# Tracksoar_1_3.net
KiCad netlist of a schematic drawn in EAGLE
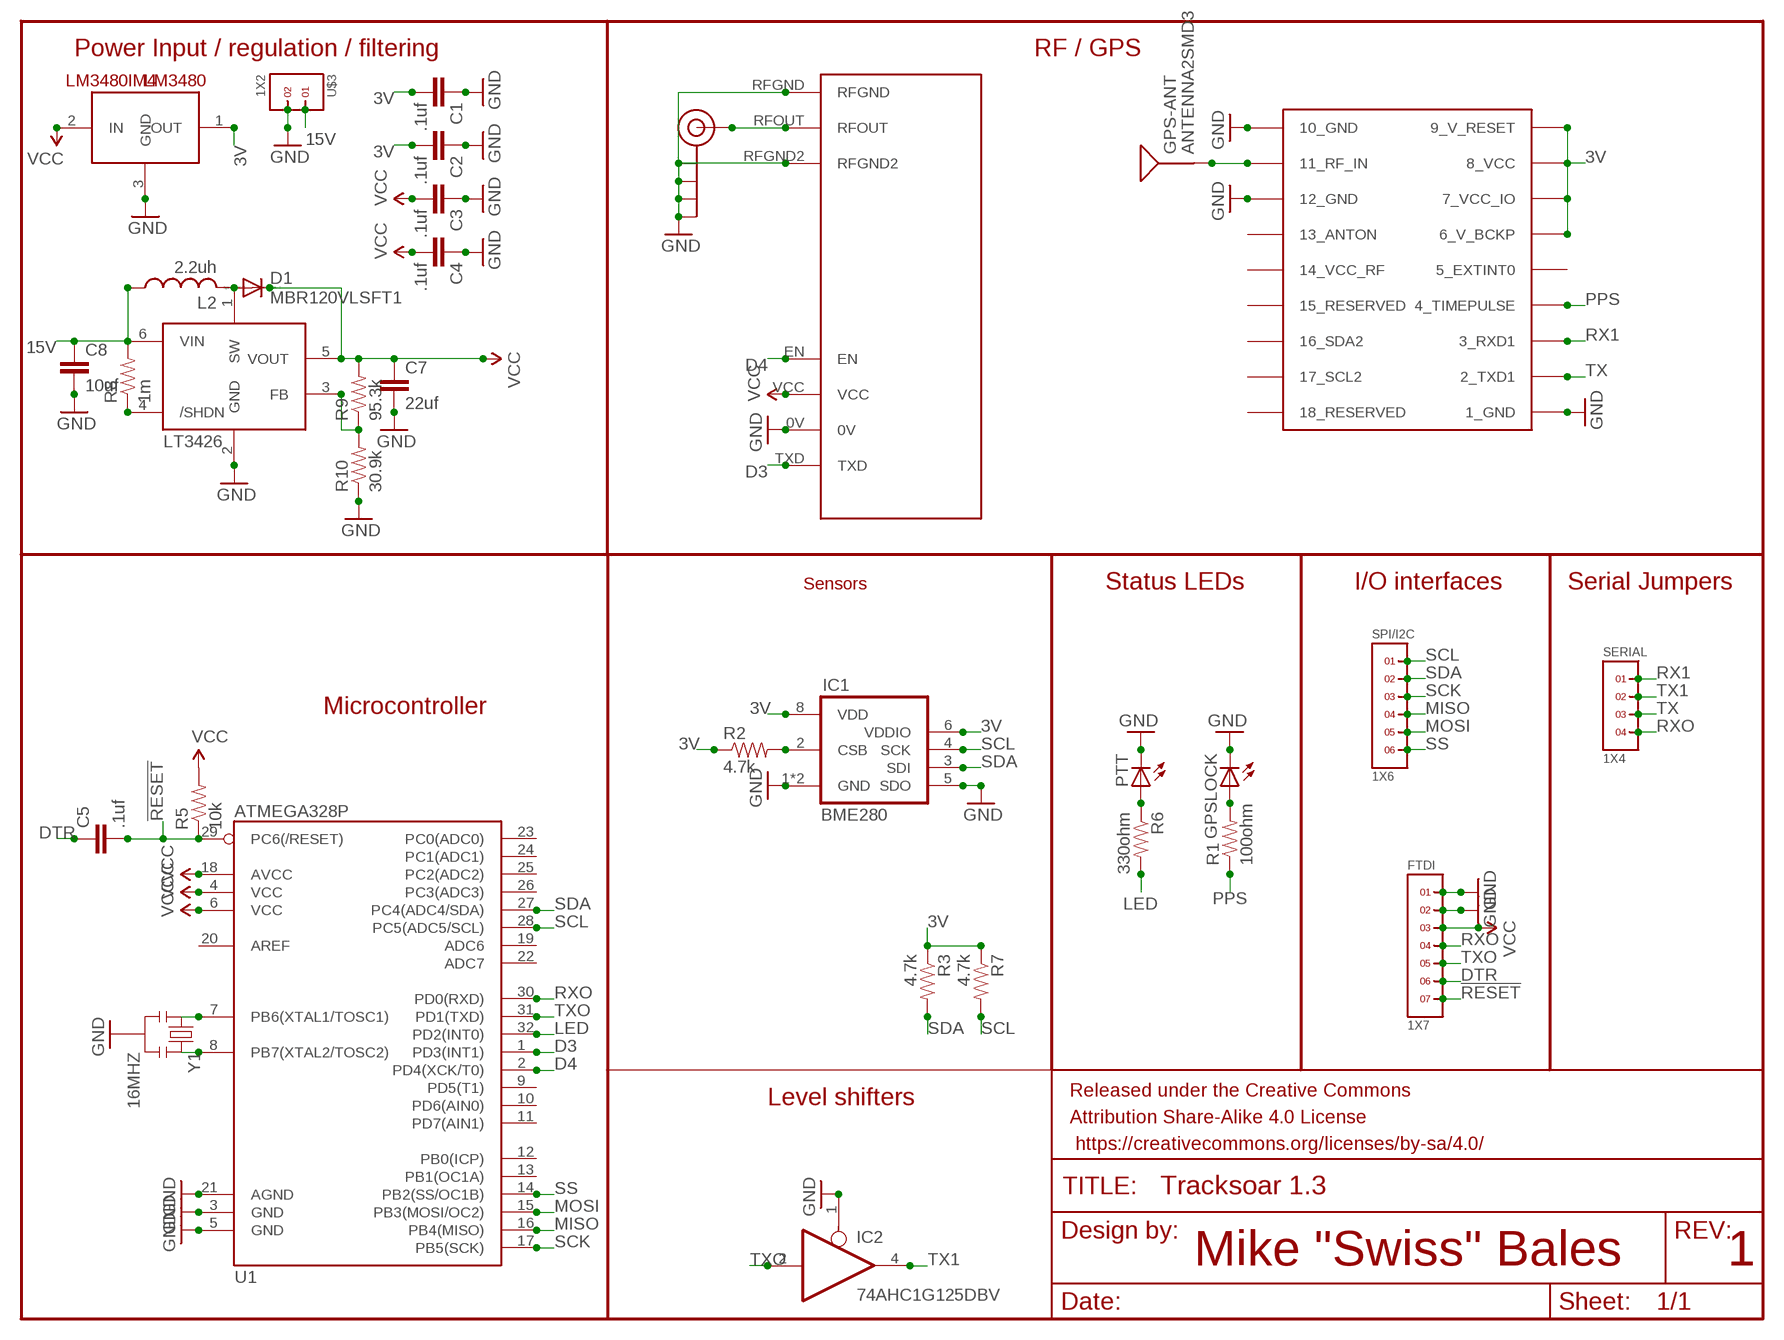
[diagram p0: schematic, sheet 1]

(export (version "E")
  (design (tool "Eeschema 10.0.6"))
  (components
    (comp (ref "C1")
      (value ".1uf")
      (footprint "eagle-import:0805")
      (libsource (lib "eagle-import") (part "CAP0805"))
    )
    (comp (ref "C2")
      (value ".1uf")
      (footprint "eagle-import:0805")
      (libsource (lib "eagle-import") (part "CAP0805"))
    )
    (comp (ref "C3")
      (value ".1uf")
      (footprint "eagle-import:0805")
      (libsource (lib "eagle-import") (part "CAP0805"))
    )
    (comp (ref "C4")
      (value ".1uf")
      (footprint "eagle-import:0805")
      (libsource (lib "eagle-import") (part "CAP0805"))
    )
    (comp (ref "C5")
      (value ".1uf")
      (footprint "eagle-import:0805")
      (libsource (lib "eagle-import") (part "CAP0805"))
    )
    (comp (ref "C7")
      (value "22uf")
      (footprint "eagle-import:0603-CAP")
      (libsource (lib "eagle-import") (part "CAP0603-CAP"))
    )
    (comp (ref "C8")
      (value "10uf")
      (footprint "eagle-import:0805")
      (libsource (lib "eagle-import") (part "CAP0805"))
    )
    (comp (ref "D1")
      (value "MBR120VLSFT1")
      (footprint "eagle-import:SOD123")
      (libsource (lib "eagle-import") (part "DIODE-SOD123"))
    )
    (comp (ref "FRAME1")
      (value "FRAME-LETTER")
      (footprint "eagle-import:CREATIVE_COMMONS")
      (libsource (lib "eagle-import") (part "FRAME-LETTER"))
    )
    (comp (ref "FTDI")
      (value "1X7")
      (footprint "eagle-import:1X7")
      (libsource (lib "eagle-import") (part "1X7"))
    )
    (comp (ref "GPS-ANT")
      (value "ANTENNA2SMD3")
      (footprint "eagle-import:ANTENNA-CHIP4")
      (libsource (lib "eagle-import") (part "ANTENNA2SMD3"))
    )
    (comp (ref "GPSLOCK")
      (value "LEDCHIP-LED0805")
      (footprint "eagle-import:CHIP-LED0805")
      (libsource (lib "eagle-import") (part "LEDCHIP-LED0805"))
    )
    (comp (ref "IC1")
      (value "BME280")
      (footprint "eagle-import:BME280")
      (libsource (lib "eagle-import") (part "BME280"))
    )
    (comp (ref "IC2")
      (value "74AHC1G125DBV")
      (footprint "eagle-import:SOT23-5")
      (libsource (lib "eagle-import") (part "741G125DBVAHC"))
    )
    (comp (ref "J$1")
      (value "SMA_EDGE")
      (footprint "eagle-import:SMA-EDGE")
      (libsource (lib "eagle-import") (part "SMA_EDGE"))
    )
    (comp (ref "L2")
      (value "2.2uh")
      (footprint "eagle-import:L1812")
      (libsource (lib "eagle-import") (part "L-USL1812"))
    )
    (comp (ref "LM3480")
      (value "LM3480IM4")
      (footprint "eagle-import:SOT23-3")
      (libsource (lib "eagle-import") (part "LM3480IM4"))
    )
    (comp (ref "LT3426")
      (value "LT3426")
      (footprint "eagle-import:SOT23-6")
      (libsource (lib "eagle-import") (part "LT3426"))
    )
    (comp (ref "PTT")
      (value "LEDCHIP-LED0805")
      (footprint "eagle-import:CHIP-LED0805")
      (libsource (lib "eagle-import") (part "LEDCHIP-LED0805"))
    )
    (comp (ref "R1")
      (value "100ohm")
      (footprint "eagle-import:0805")
      (libsource (lib "eagle-import") (part "RESISTOR0805-RES"))
    )
    (comp (ref "R2")
      (value "4.7k")
      (footprint "eagle-import:0805")
      (libsource (lib "eagle-import") (part "RESISTOR0805-RES"))
    )
    (comp (ref "R3")
      (value "4.7k")
      (footprint "eagle-import:0805")
      (libsource (lib "eagle-import") (part "RESISTOR0805-RES"))
    )
    (comp (ref "R5")
      (value "10k")
      (footprint "eagle-import:0805")
      (libsource (lib "eagle-import") (part "RESISTOR0805-RES"))
    )
    (comp (ref "R6")
      (value "330ohm")
      (footprint "eagle-import:0805")
      (libsource (lib "eagle-import") (part "RESISTOR0805-RES"))
    )
    (comp (ref "R7")
      (value "4.7k")
      (footprint "eagle-import:0805")
      (libsource (lib "eagle-import") (part "RESISTOR0805-RES"))
    )
    (comp (ref "R8")
      (value "1m")
      (footprint "eagle-import:0805")
      (libsource (lib "eagle-import") (part "RESISTOR0805-RES"))
    )
    (comp (ref "R9")
      (value "95.3k")
      (footprint "eagle-import:0603-RES")
      (libsource (lib "eagle-import") (part "RESISTOR0603"))
    )
    (comp (ref "R10")
      (value "30.9k")
      (footprint "eagle-import:0603-RES")
      (libsource (lib "eagle-import") (part "RESISTOR0603"))
    )
    (comp (ref "SERIAL")
      (value "1X4")
      (footprint "eagle-import:1X4")
      (libsource (lib "eagle-import") (part "1X4"))
    )
    (comp (ref "SPI/I2C")
      (value "1X6")
      (footprint "eagle-import:1X6")
      (libsource (lib "eagle-import") (part "1X6"))
    )
    (comp (ref "U$1")
      (value "UBLOX_MAX")
      (footprint "eagle-import:UBLOX_MAX")
      (libsource (lib "eagle-import") (part "UBLOX_MAX"))
    )
    (comp (ref "U$2")
      (value "RADIOMETRIX-HX1")
      (footprint "eagle-import:RADIOMETRIX-HX1")
      (libsource (lib "eagle-import") (part "RADIOMETRIX-HX1"))
    )
    (comp (ref "U$3")
      (value "1X2")
      (footprint "eagle-import:1X2")
      (libsource (lib "eagle-import") (part "1X2"))
    )
    (comp (ref "U1")
      (value "ATMEGA328P")
      (footprint "eagle-import:MLF32")
      (libsource (lib "eagle-import") (part "ATMEGA168MLF"))
    )
    (comp (ref "Y1")
      (value "16MHZ")
      (footprint "eagle-import:RESONATOR-SMD")
      (libsource (lib "eagle-import") (part "RESONATOR16MHZ"))
    )
  )
  (nets
    (net (code "1") (name "/3V") (class "Default")
      (node (ref "C1") (pin "2") (pinfunction "2_2") (pintype "passive"))
      (node (ref "C2") (pin "2") (pinfunction "2_2") (pintype "passive"))
      (node (ref "IC1") (pin "6") (pinfunction "VDDIO_6") (pintype "power_in"))
      (node (ref "IC1") (pin "8") (pinfunction "VDD_8") (pintype "power_in"))
      (node (ref "LM3480") (pin "1") (pinfunction "OUT_1") (pintype "bidirectional"))
      (node (ref "R2") (pin "1") (pinfunction "1_1") (pintype "passive"))
      (node (ref "R3") (pin "1") (pinfunction "1_1") (pintype "passive"))
      (node (ref "R7") (pin "1") (pinfunction "1_1") (pintype "passive"))
      (node (ref "U$1") (pin "6_V_BCKP") (pinfunction "6_V_BCKP_6_V_BCKP") (pintype "bidirectional"))
      (node (ref "U$1") (pin "7_VCC_IO") (pinfunction "7_VCC_IO_7_VCC_IO") (pintype "power_in"))
      (node (ref "U$1") (pin "8_VCC") (pinfunction "8_VCC_8_VCC") (pintype "power_in"))
      (node (ref "U$1") (pin "9_V_RESET") (pinfunction "9_V_RESET_9_V_RESET") (pintype "power_in"))
    )
    (net (code "2") (name "/15V") (class "Default")
      (node (ref "C8") (pin "1") (pinfunction "1_1") (pintype "passive"))
      (node (ref "L2") (pin "1") (pinfunction "1_1") (pintype "passive"))
      (node (ref "LT3426") (pin "6") (pinfunction "VIN_6") (pintype "input"))
      (node (ref "R8") (pin "2") (pinfunction "2_2") (pintype "passive"))
      (node (ref "U$3") (pin "1") (pinfunction "1_1") (pintype "bidirectional"))
    )
    (net (code "3") (name "/D3") (class "Default")
      (node (ref "U$2") (pin "TXD") (pinfunction "TXD_TXD") (pintype "bidirectional"))
      (node (ref "U1") (pin "1") (pinfunction "PD3(INT1)_1") (pintype "bidirectional"))
    )
    (net (code "4") (name "/D4") (class "Default")
      (node (ref "U$2") (pin "EN") (pinfunction "EN_EN") (pintype "bidirectional"))
      (node (ref "U1") (pin "2") (pinfunction "PD4(XCK/T0)_2") (pintype "bidirectional"))
    )
    (net (code "5") (name "/DTR") (class "Default")
      (node (ref "C5") (pin "1") (pinfunction "1_1") (pintype "passive"))
      (node (ref "FTDI") (pin "6") (pinfunction "6_6") (pintype "bidirectional"))
    )
    (net (code "6") (name "/LED") (class "Default")
      (node (ref "R6") (pin "2") (pinfunction "2_2") (pintype "passive"))
      (node (ref "U1") (pin "32") (pinfunction "PD2(INT0)_32") (pintype "bidirectional"))
    )
    (net (code "7") (name "/MISO") (class "Default")
      (node (ref "SPI/I2C") (pin "4") (pinfunction "4_4") (pintype "bidirectional"))
      (node (ref "U1") (pin "16") (pinfunction "PB4(MISO)_16") (pintype "bidirectional"))
    )
    (net (code "8") (name "/MOSI") (class "Default")
      (node (ref "SPI/I2C") (pin "5") (pinfunction "5_5") (pintype "bidirectional"))
      (node (ref "U1") (pin "15") (pinfunction "PB3(MOSI/OC2)_15") (pintype "bidirectional"))
    )
    (net (code "9") (name "/PPS") (class "Default")
      (node (ref "R1") (pin "1") (pinfunction "1_1") (pintype "passive"))
      (node (ref "U$1") (pin "4_TIMEPULSE") (pinfunction "4_TIMEPULSE_4_TIMEPULSE") (pintype "bidirectional"))
    )
    (net (code "10") (name "/RX1") (class "Default")
      (node (ref "SERIAL") (pin "1") (pinfunction "1_1") (pintype "bidirectional"))
      (node (ref "U$1") (pin "3_RXD1") (pinfunction "3_RXD1_3_RXD1") (pintype "bidirectional"))
    )
    (net (code "11") (name "/RXO") (class "Default")
      (node (ref "FTDI") (pin "4") (pinfunction "4_4") (pintype "bidirectional"))
      (node (ref "SERIAL") (pin "4") (pinfunction "4_4") (pintype "bidirectional"))
      (node (ref "U1") (pin "30") (pinfunction "PD0(RXD)_30") (pintype "bidirectional"))
    )
    (net (code "12") (name "/SCK") (class "Default")
      (node (ref "SPI/I2C") (pin "3") (pinfunction "3_3") (pintype "bidirectional"))
      (node (ref "U1") (pin "17") (pinfunction "PB5(SCK)_17") (pintype "bidirectional"))
    )
    (net (code "13") (name "/SCL") (class "Default")
      (node (ref "IC1") (pin "4") (pinfunction "SCK_4") (pintype "bidirectional"))
      (node (ref "R7") (pin "2") (pinfunction "2_2") (pintype "passive"))
      (node (ref "SPI/I2C") (pin "1") (pinfunction "1_1") (pintype "bidirectional"))
      (node (ref "U1") (pin "28") (pinfunction "PC5(ADC5/SCL)_28") (pintype "bidirectional"))
    )
    (net (code "14") (name "/SDA") (class "Default")
      (node (ref "IC1") (pin "3") (pinfunction "SDI_3") (pintype "bidirectional"))
      (node (ref "R3") (pin "2") (pinfunction "2_2") (pintype "passive"))
      (node (ref "SPI/I2C") (pin "2") (pinfunction "2_2") (pintype "bidirectional"))
      (node (ref "U1") (pin "27") (pinfunction "PC4(ADC4/SDA)_27") (pintype "bidirectional"))
    )
    (net (code "15") (name "/SS") (class "Default")
      (node (ref "SPI/I2C") (pin "6") (pinfunction "6_6") (pintype "bidirectional"))
      (node (ref "U1") (pin "14") (pinfunction "PB2(SS/OC1B)_14") (pintype "bidirectional"))
    )
    (net (code "16") (name "/TX") (class "Default")
      (node (ref "SERIAL") (pin "3") (pinfunction "3_3") (pintype "bidirectional"))
      (node (ref "U$1") (pin "2_TXD1") (pinfunction "2_TXD1_2_TXD1") (pintype "bidirectional"))
    )
    (net (code "17") (name "/TX1") (class "Default")
      (node (ref "IC2") (pin "4") (pinfunction "O_4") (pintype "tri_state"))
      (node (ref "SERIAL") (pin "2") (pinfunction "2_2") (pintype "bidirectional"))
    )
    (net (code "18") (name "/TXO") (class "Default")
      (node (ref "FTDI") (pin "5") (pinfunction "5_5") (pintype "bidirectional"))
      (node (ref "IC2") (pin "2") (pinfunction "I_2") (pintype "input"))
      (node (ref "U1") (pin "31") (pinfunction "PD1(TXD)_31") (pintype "bidirectional"))
    )
    (net (code "19") (name "/~{RESET}") (class "Default")
      (node (ref "C5") (pin "2") (pinfunction "2_2") (pintype "passive"))
      (node (ref "FTDI") (pin "7") (pinfunction "7_7") (pintype "bidirectional"))
      (node (ref "R5") (pin "1") (pinfunction "1_1") (pintype "passive"))
      (node (ref "U1") (pin "29") (pinfunction "PC6(/RESET)_29") (pintype "bidirectional"))
    )
    (net (code "20") (name "GND") (class "Default")
      (node (ref "C1") (pin "1") (pinfunction "1_1") (pintype "passive"))
      (node (ref "C2") (pin "1") (pinfunction "1_1") (pintype "passive"))
      (node (ref "C3") (pin "1") (pinfunction "1_1") (pintype "passive"))
      (node (ref "C4") (pin "1") (pinfunction "1_1") (pintype "passive"))
      (node (ref "C7") (pin "2") (pinfunction "2_2") (pintype "passive"))
      (node (ref "C8") (pin "2") (pinfunction "2_2") (pintype "passive"))
      (node (ref "FTDI") (pin "1") (pinfunction "1_1") (pintype "bidirectional"))
      (node (ref "FTDI") (pin "2") (pinfunction "2_2") (pintype "bidirectional"))
      (node (ref "GPSLOCK") (pin "C") (pinfunction "C_C") (pintype "passive"))
      (node (ref "IC1") (pin "1") (pinfunction "GND_1") (pintype "power_in"))
      (node (ref "IC1") (pin "5") (pinfunction "SDO_5") (pintype "input"))
      (node (ref "IC1") (pin "7") (pinfunction "GND_7") (pintype "power_in"))
      (node (ref "IC2") (pin "1") (pinfunction "OE_1") (pintype "input"))
      (node (ref "J$1") (pin "GND@0") (pinfunction "GND_GND@0") (pintype "bidirectional"))
      (node (ref "J$1") (pin "GND@1") (pinfunction "GND_GND@1") (pintype "bidirectional"))
      (node (ref "J$1") (pin "GND@2") (pinfunction "GND_GND@2") (pintype "bidirectional"))
      (node (ref "J$1") (pin "GND@3") (pinfunction "GND_GND@3") (pintype "bidirectional"))
      (node (ref "LM3480") (pin "3") (pinfunction "GND_3") (pintype "bidirectional"))
      (node (ref "LT3426") (pin "2") (pinfunction "GND_2") (pintype "power_in"))
      (node (ref "PTT") (pin "C") (pinfunction "C_C") (pintype "passive"))
      (node (ref "R10") (pin "1") (pinfunction "1_1") (pintype "passive"))
      (node (ref "U$1") (pin "10_GND") (pinfunction "10_GND_10_GND") (pintype "power_in"))
      (node (ref "U$1") (pin "12_GND") (pinfunction "12_GND_12_GND") (pintype "power_in"))
      (node (ref "U$1") (pin "1_GND") (pinfunction "1_GND_1_GND") (pintype "power_in"))
      (node (ref "U$2") (pin "0V") (pinfunction "0V_0V") (pintype "bidirectional"))
      (node (ref "U$2") (pin "RFGND") (pinfunction "RFGND_RFGND") (pintype "bidirectional"))
      (node (ref "U$2") (pin "RFGND2") (pinfunction "RFGND2_RFGND2") (pintype "bidirectional"))
      (node (ref "U$3") (pin "2") (pinfunction "2_2") (pintype "bidirectional"))
      (node (ref "U1") (pin "21") (pinfunction "AGND_21") (pintype "bidirectional"))
      (node (ref "U1") (pin "3") (pinfunction "GND_3") (pintype "bidirectional"))
      (node (ref "U1") (pin "5") (pinfunction "GND_5") (pintype "bidirectional"))
      (node (ref "Y1") (pin "2") (pinfunction "2_2") (pintype "passive"))
    )
    (net (code "21") (name "Net-(GPS-ANT-SIGNAL)") (class "Default")
      (node (ref "GPS-ANT") (pin "SIG") (pinfunction "SIGNAL_SIG") (pintype "bidirectional"))
      (node (ref "U$1") (pin "11_RF_IN") (pinfunction "11_RF_IN_11_RF_IN") (pintype "bidirectional"))
    )
    (net (code "22") (name "Net-(GPSLOCK-PadA)") (class "Default")
      (node (ref "GPSLOCK") (pin "A") (pinfunction "A_A") (pintype "passive"))
      (node (ref "R1") (pin "2") (pinfunction "2_2") (pintype "passive"))
    )
    (net (code "23") (name "Net-(IC1-CSB)") (class "Default")
      (node (ref "IC1") (pin "2") (pinfunction "CSB_2") (pintype "input"))
      (node (ref "R2") (pin "2") (pinfunction "2_2") (pintype "passive"))
    )
    (net (code "24") (name "Net-(J$1-SIGNAL)") (class "Default")
      (node (ref "J$1") (pin "SIG") (pinfunction "SIGNAL_SIG") (pintype "bidirectional"))
      (node (ref "U$2") (pin "RFOUT") (pinfunction "RFOUT_RFOUT") (pintype "bidirectional"))
    )
    (net (code "25") (name "Net-(LT3426-FB)") (class "Default")
      (node (ref "LT3426") (pin "3") (pinfunction "FB_3") (pintype "input"))
      (node (ref "R10") (pin "2") (pinfunction "2_2") (pintype "passive"))
      (node (ref "R9") (pin "1") (pinfunction "1_1") (pintype "passive"))
    )
    (net (code "26") (name "Net-(LT3426-SW)") (class "Default")
      (node (ref "D1") (pin "A") (pinfunction "A_A") (pintype "passive"))
      (node (ref "L2") (pin "2") (pinfunction "2_2") (pintype "passive"))
      (node (ref "LT3426") (pin "1") (pinfunction "SW_1") (pintype "output"))
    )
    (net (code "27") (name "Net-(LT3426-{slash}SHDN)") (class "Default")
      (node (ref "LT3426") (pin "4") (pinfunction "/SHDN_4") (pintype "input"))
      (node (ref "R8") (pin "1") (pinfunction "1_1") (pintype "passive"))
    )
    (net (code "28") (name "Net-(PTT-PadA)") (class "Default")
      (node (ref "PTT") (pin "A") (pinfunction "A_A") (pintype "passive"))
      (node (ref "R6") (pin "1") (pinfunction "1_1") (pintype "passive"))
    )
    (net (code "29") (name "Net-(U1-PB6(XTAL1{slash}TOSC1))") (class "Default")
      (node (ref "U1") (pin "7") (pinfunction "PB6(XTAL1/TOSC1)_7") (pintype "bidirectional"))
      (node (ref "Y1") (pin "1") (pinfunction "1_1") (pintype "passive"))
    )
    (net (code "30") (name "Net-(U1-PB7(XTAL2{slash}TOSC2))") (class "Default")
      (node (ref "U1") (pin "8") (pinfunction "PB7(XTAL2/TOSC2)_8") (pintype "bidirectional"))
      (node (ref "Y1") (pin "3") (pinfunction "3_3") (pintype "passive"))
    )
    (net (code "31") (name "VCC") (class "Default")
      (node (ref "C3") (pin "2") (pinfunction "2_2") (pintype "passive"))
      (node (ref "C4") (pin "2") (pinfunction "2_2") (pintype "passive"))
      (node (ref "C7") (pin "1") (pinfunction "1_1") (pintype "passive"))
      (node (ref "D1") (pin "C") (pinfunction "C_C") (pintype "passive"))
      (node (ref "FTDI") (pin "3") (pinfunction "3_3") (pintype "bidirectional"))
      (node (ref "LM3480") (pin "2") (pinfunction "IN_2") (pintype "bidirectional"))
      (node (ref "LT3426") (pin "5") (pinfunction "VOUT_5") (pintype "output"))
      (node (ref "R5") (pin "2") (pinfunction "2_2") (pintype "passive"))
      (node (ref "R9") (pin "2") (pinfunction "2_2") (pintype "passive"))
      (node (ref "U$2") (pin "VCC") (pinfunction "VCC_VCC") (pintype "bidirectional"))
      (node (ref "U1") (pin "18") (pinfunction "AVCC_18") (pintype "bidirectional"))
      (node (ref "U1") (pin "4") (pinfunction "VCC_4") (pintype "bidirectional"))
      (node (ref "U1") (pin "6") (pinfunction "VCC_6") (pintype "bidirectional"))
    )
    (net (code "32") (name "unconnected-(U$1-Pad5_EXTINT0)") (class "Default")
      (node (ref "U$1") (pin "5_EXTINT0") (pinfunction "5_EXTINT0_5_EXTINT0") (pintype "bidirectional"))
    )
    (net (code "33") (name "unconnected-(U$1-Pad13_ANTON)") (class "Default")
      (node (ref "U$1") (pin "13_ANTON") (pinfunction "13_ANTON_13_ANTON") (pintype "bidirectional"))
    )
    (net (code "34") (name "unconnected-(U$1-Pad14_VCC_RF)") (class "Default")
      (node (ref "U$1") (pin "14_VCC_RF") (pinfunction "14_VCC_RF_14_VCC_RF") (pintype "bidirectional"))
    )
    (net (code "35") (name "unconnected-(U$1-Pad15_RESERVED)") (class "Default")
      (node (ref "U$1") (pin "15_RESERVED") (pinfunction "15_RESERVED_15_RESERVED") (pintype "bidirectional"))
    )
    (net (code "36") (name "unconnected-(U$1-Pad16_SDA2)") (class "Default")
      (node (ref "U$1") (pin "16_SDA2") (pinfunction "16_SDA2_16_SDA2") (pintype "bidirectional"))
    )
    (net (code "37") (name "unconnected-(U$1-Pad17_SCL2)") (class "Default")
      (node (ref "U$1") (pin "17_SCL2") (pinfunction "17_SCL2_17_SCL2") (pintype "bidirectional"))
    )
    (net (code "38") (name "unconnected-(U$1-Pad18_RESERVED)") (class "Default")
      (node (ref "U$1") (pin "18_RESERVED") (pinfunction "18_RESERVED_18_RESERVED") (pintype "bidirectional"))
    )
    (net (code "39") (name "unconnected-(U1-ADC6-Pad19)") (class "Default")
      (node (ref "U1") (pin "19") (pinfunction "ADC6_19") (pintype "bidirectional"))
    )
    (net (code "40") (name "unconnected-(U1-ADC7-Pad22)") (class "Default")
      (node (ref "U1") (pin "22") (pinfunction "ADC7_22") (pintype "bidirectional"))
    )
    (net (code "41") (name "unconnected-(U1-AREF-Pad20)") (class "Default")
      (node (ref "U1") (pin "20") (pinfunction "AREF_20") (pintype "bidirectional"))
    )
    (net (code "42") (name "unconnected-(U1-PB0(ICP)-Pad12)") (class "Default")
      (node (ref "U1") (pin "12") (pinfunction "PB0(ICP)_12") (pintype "bidirectional"))
    )
    (net (code "43") (name "unconnected-(U1-PB1(OC1A)-Pad13)") (class "Default")
      (node (ref "U1") (pin "13") (pinfunction "PB1(OC1A)_13") (pintype "bidirectional"))
    )
    (net (code "44") (name "unconnected-(U1-PC0(ADC0)-Pad23)") (class "Default")
      (node (ref "U1") (pin "23") (pinfunction "PC0(ADC0)_23") (pintype "bidirectional"))
    )
    (net (code "45") (name "unconnected-(U1-PC1(ADC1)-Pad24)") (class "Default")
      (node (ref "U1") (pin "24") (pinfunction "PC1(ADC1)_24") (pintype "bidirectional"))
    )
    (net (code "46") (name "unconnected-(U1-PC2(ADC2)-Pad25)") (class "Default")
      (node (ref "U1") (pin "25") (pinfunction "PC2(ADC2)_25") (pintype "bidirectional"))
    )
    (net (code "47") (name "unconnected-(U1-PC3(ADC3)-Pad26)") (class "Default")
      (node (ref "U1") (pin "26") (pinfunction "PC3(ADC3)_26") (pintype "bidirectional"))
    )
    (net (code "48") (name "unconnected-(U1-PD5(T1)-Pad9)") (class "Default")
      (node (ref "U1") (pin "9") (pinfunction "PD5(T1)_9") (pintype "bidirectional"))
    )
    (net (code "49") (name "unconnected-(U1-PD6(AIN0)-Pad10)") (class "Default")
      (node (ref "U1") (pin "10") (pinfunction "PD6(AIN0)_10") (pintype "bidirectional"))
    )
    (net (code "50") (name "unconnected-(U1-PD7(AIN1)-Pad11)") (class "Default")
      (node (ref "U1") (pin "11") (pinfunction "PD7(AIN1)_11") (pintype "bidirectional"))
    )
  )
)
